# Supply.net
KiCad netlist of a schematic drawn in Altium Designer
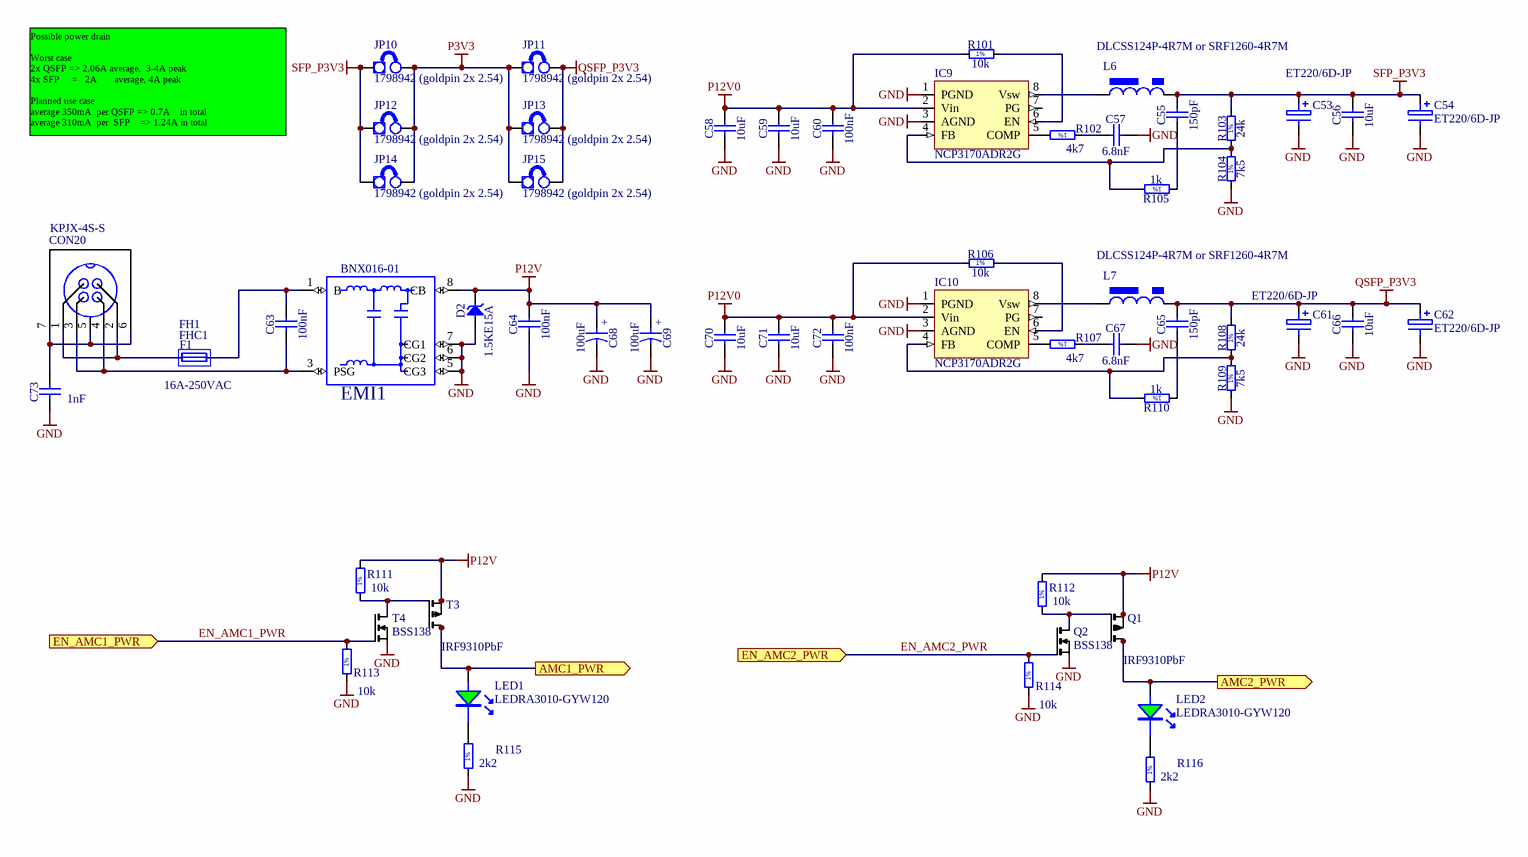
[diagram p0: Supply.SchDoc]

(export (version "E")
  (design (tool "Eeschema 10.0.6"))
  (components
    (comp (ref "C53")
      (value "ET220/6D-JP")
      (footprint "2917_SMDD")
      (description "Tantalium Capacitor")
      (libsource (lib "LIBRARY_SCH") (part "CAP_TANTALIUM"))
    )
    (comp (ref "C54")
      (value "ET220/6D-JP")
      (footprint "2917_SMDD")
      (description "Tantalium Capacitor")
      (libsource (lib "LIBRARY_SCH") (part "CAP_TANTALIUM"))
    )
    (comp (ref "C55")
      (value "150pF")
      (footprint "CAPC1608X87N")
      (description "Non-polarised capacitor")
      (fields
        (field (name "PART NUMBER") "CC0603_150PF_50V_5%_NP0")
        (field (name "VOLTAGE") "50V")
        (field (name "AUTHOR") "CERN DEM JLC")
      )
      (libsource (lib "Capacitors") (part "Capacitor - non polarized"))
    )
    (comp (ref "C56")
      (value "10uF")
      (footprint "CAPC2012X135N")
      (description "Non-polarised capacitor")
      (fields
        (field (name "PART NUMBER") "CC0805_10UF_10V_10%_X7R")
        (field (name "VOLTAGE") "10V")
        (field (name "AUTHOR") "CERN DEM JLC")
      )
      (libsource (lib "Capacitors") (part "Capacitor - non polarized"))
    )
    (comp (ref "C57")
      (value "6.8nF")
      (footprint "CAPC1608X87N")
      (description "Non-polarised capacitor")
      (fields
        (field (name "PART NUMBER") "CC0603_6.8NF_50V_5%_C0G")
        (field (name "VOLTAGE") "50V")
        (field (name "AUTHOR") "CERN DEM JLC")
      )
      (libsource (lib "Capacitors") (part "Capacitor - non polarized"))
    )
    (comp (ref "C58")
      (value "10uF")
      (footprint "CAPC3216X140N")
      (description "Non-polarised capacitor")
      (fields
        (field (name "PART NUMBER") "CC1206_10UF_16V_10%_X7R")
        (field (name "VOLTAGE") "16V")
        (field (name "AUTHOR") "CERN DEM JLC")
      )
      (libsource (lib "Capacitors") (part "Capacitor - non polarized"))
    )
    (comp (ref "C59")
      (value "10uF")
      (footprint "CAPC3216X140N")
      (description "Non-polarised capacitor")
      (fields
        (field (name "PART NUMBER") "CC1206_10UF_16V_10%_X7R")
        (field (name "VOLTAGE") "16V")
        (field (name "AUTHOR") "CERN DEM JLC")
      )
      (libsource (lib "Capacitors") (part "Capacitor - non polarized"))
    )
    (comp (ref "C60")
      (value "100nF")
      (footprint "CAPC1005X55N")
      (description "Non-polarised capacitor")
      (fields
        (field (name "PART NUMBER") "CC0402_100NF_16V_10%_X5R")
        (field (name "VOLTAGE") "16V")
        (field (name "AUTHOR") "CERN DEM JLC")
      )
      (libsource (lib "Capacitors") (part "Capacitor - non polarized"))
    )
    (comp (ref "C61")
      (value "ET220/6D-JP")
      (footprint "2917_SMDD")
      (description "Tantalium Capacitor")
      (libsource (lib "LIBRARY_SCH") (part "CAP_TANTALIUM"))
    )
    (comp (ref "C62")
      (value "ET220/6D-JP")
      (footprint "2917_SMDD")
      (description "Tantalium Capacitor")
      (libsource (lib "LIBRARY_SCH") (part "CAP_TANTALIUM"))
    )
    (comp (ref "C63")
      (value "100nF")
      (footprint "CAPC1005X55N")
      (description "Non-polarised capacitor")
      (fields
        (field (name "PART NUMBER") "CC0402_100NF_16V_10%_X5R")
        (field (name "VOLTAGE") "16V")
        (field (name "AUTHOR") "CERN DEM JLC")
      )
      (libsource (lib "Capacitors") (part "Capacitor - non polarized"))
    )
    (comp (ref "C64")
      (value "100nF")
      (footprint "CAPC1005X55N")
      (description "Non-polarised capacitor")
      (fields
        (field (name "PART NUMBER") "CC0402_100NF_16V_10%_X5R")
        (field (name "VOLTAGE") "16V")
        (field (name "AUTHOR") "CERN DEM JLC")
      )
      (libsource (lib "Capacitors") (part "Capacitor - non polarized"))
    )
    (comp (ref "C65")
      (value "150pF")
      (footprint "CAPC1608X87N")
      (description "Non-polarised capacitor")
      (fields
        (field (name "PART NUMBER") "CC0603_150PF_50V_5%_NP0")
        (field (name "VOLTAGE") "50V")
        (field (name "AUTHOR") "CERN DEM JLC")
      )
      (libsource (lib "Capacitors") (part "Capacitor - non polarized"))
    )
    (comp (ref "C66")
      (value "10uF")
      (footprint "CAPC2012X135N")
      (description "Non-polarised capacitor")
      (fields
        (field (name "PART NUMBER") "CC0805_10UF_10V_10%_X7R")
        (field (name "VOLTAGE") "10V")
        (field (name "AUTHOR") "CERN DEM JLC")
      )
      (libsource (lib "Capacitors") (part "Capacitor - non polarized"))
    )
    (comp (ref "C67")
      (value "6.8nF")
      (footprint "CAPC1608X87N")
      (description "Non-polarised capacitor")
      (fields
        (field (name "PART NUMBER") "CC0603_6.8NF_50V_5%_C0G")
        (field (name "VOLTAGE") "50V")
        (field (name "AUTHOR") "CERN DEM JLC")
      )
      (libsource (lib "Capacitors") (part "Capacitor - non polarized"))
    )
    (comp (ref "C68")
      (value "100uF")
      (footprint "CAPMP7343X430N")
      (description "Polarised capacitor")
      (fields
        (field (name "PART NUMBER") "CTE7343-43_100UF_20V_10%_LESR0150")
        (field (name "VOLTAGE") "20V")
        (field (name "AUTHOR") "CERN DEM JLC")
      )
      (libsource (lib "Capacitors") (part "Capacitor - polarized"))
    )
    (comp (ref "C69")
      (value "100uF")
      (footprint "CAPMP7343X430N")
      (description "Polarised capacitor")
      (fields
        (field (name "PART NUMBER") "CTE7343-43_100UF_20V_10%_LESR0150")
        (field (name "VOLTAGE") "20V")
        (field (name "AUTHOR") "CERN DEM JLC")
      )
      (libsource (lib "Capacitors") (part "Capacitor - polarized"))
    )
    (comp (ref "C70")
      (value "10uF")
      (footprint "CAPC3216X140N")
      (description "Non-polarised capacitor")
      (fields
        (field (name "PART NUMBER") "CC1206_10UF_16V_10%_X7R")
        (field (name "VOLTAGE") "16V")
        (field (name "AUTHOR") "CERN DEM JLC")
      )
      (libsource (lib "Capacitors") (part "Capacitor - non polarized"))
    )
    (comp (ref "C71")
      (value "10uF")
      (footprint "CAPC3216X140N")
      (description "Non-polarised capacitor")
      (fields
        (field (name "PART NUMBER") "CC1206_10UF_16V_10%_X7R")
        (field (name "VOLTAGE") "16V")
        (field (name "AUTHOR") "CERN DEM JLC")
      )
      (libsource (lib "Capacitors") (part "Capacitor - non polarized"))
    )
    (comp (ref "C72")
      (value "100nF")
      (footprint "CAPC1005X55N")
      (description "Non-polarised capacitor")
      (fields
        (field (name "PART NUMBER") "CC0402_100NF_16V_10%_X5R")
        (field (name "VOLTAGE") "16V")
        (field (name "AUTHOR") "CERN DEM JLC")
      )
      (libsource (lib "Capacitors") (part "Capacitor - non polarized"))
    )
    (comp (ref "C73")
      (value "1nF")
      (footprint "CAPC3216X140N")
      (description "Non-polarised capacitor")
      (fields
        (field (name "PART NUMBER") "CC1206_1NF_100V_5%_NP0")
        (field (name "VOLTAGE") "100V")
        (field (name "AUTHOR") "CERN DEM JLC")
      )
      (libsource (lib "Capacitors") (part "Capacitor - non polarized"))
    )
    (comp (ref "CON20")
      (value "KPJX-4S-S")
      (footprint "CON_KPJX-4S-S")
      (description "7.5A DC connector")
      (libsource (lib "LIBRARY_SCH") (part "CON_DC_7.5A_4pin"))
    )
    (comp (ref "D2")
      (value "1.5KE15A")
      (footprint "VISHAY_1.5KE")
      (description "Transient Voltage Suppressor Diode (Uni-Directional)")
      (fields
        (field (name "VOLTAGE") "15V")
        (field (name "POWER") "1500W")
        (field (name "AUTHOR") "CERN DEM JLC")
      )
      (libsource (lib "ICs And Semiconductors") (part "Diode TVS Uni-Directional"))
    )
    (comp (ref "EMI1")
      (value "BNX016-01")
      (footprint "BNX016-01")
      (description "FILTER EMI 50MOHM 15A .1M-1GHZ")
      (fields (field (name "MANF") "MURATA") (field (name "OWNER") "3709"))
      (libsource (lib "LIBRARY_SCH") (part "L_CMC_BNX016-01.1"))
    )
    (comp (ref "F1")
      (value "16A-250VAC")
      (footprint "FUSE_5X20_GLASS_h")
      (description "Fuse")
      (fields
        (field (name "PART NUMBER") "FUSE_SCHURTER_0034.3129_h")
        (field (name "MANUFACTURER") "SCHURTER")
        (field (name "AUTHOR") "CERN DEM JLC")
      )
      (libsource (lib "Eletro-mechanical") (part "Fuse No Pin"))
    )
    (comp (ref "FH1")
      (value "Fuse Holder")
      (footprint "FUSH_SCHURTER_OGN")
      (fields
        (field (name "PART NUMBER") "FUSH_SCHURTER-OGN_0031.8211")
        (field (name "MANUFACTURER") "SCHURTER")
        (field (name "MANUFACTURER PART NUMBER") "0031.8211")
        (field (name "AUTHOR") "CERN DEM JLC")
      )
      (libsource (lib "Eletro-mechanical") (part "Fuse Holder"))
    )
    (comp (ref "FHC1")
      (value "Fuse Holder Cover No Pin")
      (footprint "FUSHC_SCHURTER_0853.0551")
      (fields
        (field (name "PART NUMBER") "FUSHC_SCHURTER_0853.0551")
        (field (name "MANUFACTURER") "SCHURTER")
        (field (name "MANUFACTURER PART NUMBER") "0853.0551")
        (field (name "AUTHOR") "CERN DEM JLC")
      )
      (libsource (lib "Eletro-mechanical") (part "Fuse Holder Cover No Pin"))
    )
    (comp (ref "IC9")
      (value "NCP3170ADR2G")
      (footprint "so-8")
      (description "4.5V to 18V, 3A synch buck")
      (libsource (lib "LIBRARY_SCH") (part "PWM_NCP3170"))
    )
    (comp (ref "IC10")
      (value "NCP3170ADR2G")
      (footprint "so-8")
      (description "4.5V to 18V, 3A synch buck")
      (libsource (lib "LIBRARY_SCH") (part "PWM_NCP3170"))
    )
    (comp (ref "JP10")
      (value "1798942 (goldpin 2x 2.54)")
      (footprint "HEADER2x1 2.54mm")
      (description "Jumper")
      (libsource (lib "Misc") (part "JUMPER"))
    )
    (comp (ref "JP11")
      (value "1798942 (goldpin 2x 2.54)")
      (footprint "HEADER2x1 2.54mm")
      (description "Jumper")
      (libsource (lib "Misc") (part "JUMPER"))
    )
    (comp (ref "JP12")
      (value "1798942 (goldpin 2x 2.54)")
      (footprint "HEADER2x1 2.54mm")
      (description "Jumper")
      (libsource (lib "Misc") (part "JUMPER"))
    )
    (comp (ref "JP13")
      (value "1798942 (goldpin 2x 2.54)")
      (footprint "HEADER2x1 2.54mm")
      (description "Jumper")
      (libsource (lib "Misc") (part "JUMPER"))
    )
    (comp (ref "JP14")
      (value "1798942 (goldpin 2x 2.54)")
      (footprint "HEADER2x1 2.54mm")
      (description "Jumper")
      (libsource (lib "Misc") (part "JUMPER"))
    )
    (comp (ref "JP15")
      (value "1798942 (goldpin 2x 2.54)")
      (footprint "HEADER2x1 2.54mm")
      (description "Jumper")
      (libsource (lib "Misc") (part "JUMPER"))
    )
    (comp (ref "L6")
      (value "DLCSS124P-4R7M or SRF1260-4R7M")
      (footprint "choke_DLCSS124")
      (description "Shielded Ferrite base SMD Power Choke DLCSS124P Series 4.7uH, 20%, 5.7A, 0.018R, 750pcs/reel")
      (libsource (lib "LIBRARY_SCH") (part "L_POWER_CSS124_6.8uH"))
    )
    (comp (ref "L7")
      (value "DLCSS124P-4R7M or SRF1260-4R7M")
      (footprint "choke_DLCSS124")
      (description "Shielded Ferrite base SMD Power Choke DLCSS124P Series 4.7uH, 20%, 5.7A, 0.018R, 750pcs/reel")
      (libsource (lib "LIBRARY_SCH") (part "L_POWER_CSS124_6.8uH"))
    )
    (comp (ref "LED1")
      (value "LEDRA3010-GYW120")
      (footprint "LED_KPA3010_G")
      (description "LED (Maritex)")
      (libsource (lib "LIBRARY_SCH") (part "LED_SMD_90deg_G"))
    )
    (comp (ref "LED2")
      (value "LEDRA3010-GYW120")
      (footprint "LED_KPA3010_G")
      (description "LED (Maritex)")
      (libsource (lib "LIBRARY_SCH") (part "LED_SMD_90deg_G"))
    )
    (comp (ref "Q1")
      (value "IRF9310PbF")
      (footprint "so-8")
      (description "PMOS 30V, 4.6mR, 20A, 2.5W")
      (libsource (lib "LIBRARY_SCH") (part "Q_IRF9310"))
    )
    (comp (ref "Q2")
      (value "BSS138")
      (footprint "SOT95P251X112-3N")
      (libsource (lib "LIBRARY_SCH") (part "Q_BSS138"))
    )
    (comp (ref "R101")
      (value "10k")
      (footprint "RESC1005X40N")
      (description "Resistor - 1%")
      (fields
        (field (name "PART NUMBER") "R0402_10K_1%_0.0625W_100PPM")
        (field (name "POWER") "0.0625W")
        (field (name "AUTHOR") "CERN DEM JLC")
      )
      (libsource (lib "Resistors") (part "Resistor - 1%"))
    )
    (comp (ref "R102")
      (value "4k7")
      (footprint "RESC1005X40N")
      (description "Resistor - 1%")
      (fields
        (field (name "PART NUMBER") "R0402_4K7_1%_0.0625W_100PPM")
        (field (name "POWER") "0.0625W")
        (field (name "AUTHOR") "CERN DEM JLC")
      )
      (libsource (lib "Resistors") (part "Resistor - 1%"))
    )
    (comp (ref "R103")
      (value "24k")
      (footprint "RESC1608X55N")
      (description "Resistor - 1%")
      (fields
        (field (name "PART NUMBER") "R0603_24K_1%_0.1W_100PPM")
        (field (name "POWER") "0.1W")
        (field (name "AUTHOR") "CERN DEM JLC")
      )
      (libsource (lib "Resistors") (part "Resistor - 1%"))
    )
    (comp (ref "R104")
      (value "7k5")
      (footprint "RESC1608X55N")
      (description "Resistor - 1%")
      (fields
        (field (name "PART NUMBER") "R0603_7K5_1%_0.1W_100PPM")
        (field (name "POWER") "0.1W")
        (field (name "AUTHOR") "CERN DEM JLC")
      )
      (libsource (lib "Resistors") (part "Resistor - 1%"))
    )
    (comp (ref "R105")
      (value "1k")
      (footprint "RESC1005X40N")
      (description "Resistor - 1%")
      (fields
        (field (name "PART NUMBER") "R0402_1K_1%_0.0625W_100PPM")
        (field (name "POWER") "0.0625W")
        (field (name "AUTHOR") "CERN DEM JLC")
      )
      (libsource (lib "Resistors") (part "Resistor - 1%"))
    )
    (comp (ref "R106")
      (value "10k")
      (footprint "RESC1005X40N")
      (description "Resistor - 1%")
      (fields
        (field (name "PART NUMBER") "R0402_10K_1%_0.0625W_100PPM")
        (field (name "POWER") "0.0625W")
        (field (name "AUTHOR") "CERN DEM JLC")
      )
      (libsource (lib "Resistors") (part "Resistor - 1%"))
    )
    (comp (ref "R107")
      (value "4k7")
      (footprint "RESC1005X40N")
      (description "Resistor - 1%")
      (fields
        (field (name "PART NUMBER") "R0402_4K7_1%_0.0625W_100PPM")
        (field (name "POWER") "0.0625W")
        (field (name "AUTHOR") "CERN DEM JLC")
      )
      (libsource (lib "Resistors") (part "Resistor - 1%"))
    )
    (comp (ref "R108")
      (value "24k")
      (footprint "RESC1608X55N")
      (description "Resistor - 1%")
      (fields
        (field (name "PART NUMBER") "R0603_24K_1%_0.1W_100PPM")
        (field (name "POWER") "0.1W")
        (field (name "AUTHOR") "CERN DEM JLC")
      )
      (libsource (lib "Resistors") (part "Resistor - 1%"))
    )
    (comp (ref "R109")
      (value "7k5")
      (footprint "RESC1608X55N")
      (description "Resistor - 1%")
      (fields
        (field (name "PART NUMBER") "R0603_7K5_1%_0.1W_100PPM")
        (field (name "POWER") "0.1W")
        (field (name "AUTHOR") "CERN DEM JLC")
      )
      (libsource (lib "Resistors") (part "Resistor - 1%"))
    )
    (comp (ref "R110")
      (value "1k")
      (footprint "RESC1005X40N")
      (description "Resistor - 1%")
      (fields
        (field (name "PART NUMBER") "R0402_1K_1%_0.0625W_100PPM")
        (field (name "POWER") "0.0625W")
        (field (name "AUTHOR") "CERN DEM JLC")
      )
      (libsource (lib "Resistors") (part "Resistor - 1%"))
    )
    (comp (ref "R111")
      (value "10k")
      (footprint "RESC1005X40N")
      (description "Resistor - 1%")
      (fields
        (field (name "PART NUMBER") "R0402_10K_1%_0.0625W_100PPM")
        (field (name "POWER") "0.0625W")
        (field (name "AUTHOR") "CERN DEM JLC")
      )
      (libsource (lib "Resistors") (part "Resistor - 1%"))
    )
    (comp (ref "R112")
      (value "10k")
      (footprint "RESC1005X40N")
      (description "Resistor - 1%")
      (fields
        (field (name "PART NUMBER") "R0402_10K_1%_0.0625W_100PPM")
        (field (name "POWER") "0.0625W")
        (field (name "AUTHOR") "CERN DEM JLC")
      )
      (libsource (lib "Resistors") (part "Resistor - 1%"))
    )
    (comp (ref "R113")
      (value "10k")
      (footprint "RESC1005X40N")
      (description "Resistor - 1%")
      (fields
        (field (name "PART NUMBER") "R0402_10K_1%_0.0625W_100PPM")
        (field (name "POWER") "0.0625W")
        (field (name "AUTHOR") "CERN DEM JLC")
      )
      (libsource (lib "Resistors") (part "Resistor - 1%"))
    )
    (comp (ref "R114")
      (value "10k")
      (footprint "RESC1005X40N")
      (description "Resistor - 1%")
      (fields
        (field (name "PART NUMBER") "R0402_10K_1%_0.0625W_100PPM")
        (field (name "POWER") "0.0625W")
        (field (name "AUTHOR") "CERN DEM JLC")
      )
      (libsource (lib "Resistors") (part "Resistor - 1%"))
    )
    (comp (ref "R115")
      (value "2k2")
      (footprint "RESC1005X40N")
      (description "Resistor - 1%")
      (fields
        (field (name "PART NUMBER") "R0402_2K2_1%_0.0625W_100PPM")
        (field (name "POWER") "0.0625W")
        (field (name "AUTHOR") "CERN DEM JLC")
      )
      (libsource (lib "Resistors") (part "Resistor - 1%"))
    )
    (comp (ref "R116")
      (value "2k2")
      (footprint "RESC1005X40N")
      (description "Resistor - 1%")
      (fields
        (field (name "PART NUMBER") "R0402_2K2_1%_0.0625W_100PPM")
        (field (name "POWER") "0.0625W")
        (field (name "AUTHOR") "CERN DEM JLC")
      )
      (libsource (lib "Resistors") (part "Resistor - 1%"))
    )
    (comp (ref "T3")
      (value "IRF9310PbF")
      (footprint "so-8")
      (description "PMOS 30V, 4.6mR, 20A, 2.5W")
      (libsource (lib "LIBRARY_SCH") (part "Q_IRF9310"))
    )
    (comp (ref "T4")
      (value "BSS138")
      (footprint "SOT95P251X112-3N")
      (libsource (lib "LIBRARY_SCH") (part "Q_BSS138"))
    )
  )
  (nets
    (net (code "1") (name "/AMC1_PWR") (class "Default")
      (node (ref "LED1") (pin "A") (pinfunction "A_A") (pintype "passive"))
      (node (ref "T3") (pin "5") (pinfunction "D1_5") (pintype "open_collector"))
      (node (ref "T3") (pin "6") (pinfunction "D1_6") (pintype "open_collector"))
      (node (ref "T3") (pin "7") (pinfunction "D1_7") (pintype "open_collector"))
      (node (ref "T3") (pin "8") (pinfunction "D1_8") (pintype "open_collector"))
    )
    (net (code "2") (name "/AMC2_PWR") (class "Default")
      (node (ref "LED2") (pin "A") (pinfunction "A_A") (pintype "passive"))
      (node (ref "Q1") (pin "5") (pinfunction "D1_5") (pintype "open_collector"))
      (node (ref "Q1") (pin "6") (pinfunction "D1_6") (pintype "open_collector"))
      (node (ref "Q1") (pin "7") (pinfunction "D1_7") (pintype "open_collector"))
      (node (ref "Q1") (pin "8") (pinfunction "D1_8") (pintype "open_collector"))
    )
    (net (code "3") (name "/EN_AMC1_PWR") (class "Default")
      (node (ref "R113") (pin "2") (pinfunction "2_2") (pintype "passive"))
      (node (ref "T4") (pin "1") (pinfunction "G_1") (pintype "input"))
    )
    (net (code "4") (name "/EN_AMC2_PWR") (class "Default")
      (node (ref "Q2") (pin "1") (pinfunction "G_1") (pintype "input"))
      (node (ref "R114") (pin "2") (pinfunction "2_2") (pintype "passive"))
    )
    (net (code "5") (name "GND") (class "Default")
      (node (ref "C53") (pin "2") (pinfunction "2_2") (pintype "passive"))
      (node (ref "C54") (pin "2") (pinfunction "2_2") (pintype "passive"))
      (node (ref "C56") (pin "1") (pinfunction "1_1") (pintype "passive"))
      (node (ref "C57") (pin "2") (pinfunction "2_2") (pintype "passive"))
      (node (ref "C58") (pin "1") (pinfunction "1_1") (pintype "passive"))
      (node (ref "C59") (pin "1") (pinfunction "1_1") (pintype "passive"))
      (node (ref "C60") (pin "1") (pinfunction "1_1") (pintype "passive"))
      (node (ref "C61") (pin "2") (pinfunction "2_2") (pintype "passive"))
      (node (ref "C62") (pin "2") (pinfunction "2_2") (pintype "passive"))
      (node (ref "C64") (pin "1") (pinfunction "1_1") (pintype "passive"))
      (node (ref "C66") (pin "1") (pinfunction "1_1") (pintype "passive"))
      (node (ref "C67") (pin "2") (pinfunction "2_2") (pintype "passive"))
      (node (ref "C68") (pin "2") (pinfunction "2_2") (pintype "passive"))
      (node (ref "C69") (pin "2") (pinfunction "2_2") (pintype "passive"))
      (node (ref "C70") (pin "1") (pinfunction "1_1") (pintype "passive"))
      (node (ref "C71") (pin "1") (pinfunction "1_1") (pintype "passive"))
      (node (ref "C72") (pin "1") (pinfunction "1_1") (pintype "passive"))
      (node (ref "C73") (pin "1") (pinfunction "1_1") (pintype "passive"))
      (node (ref "D2") (pin "2") (pinfunction "A_2") (pintype "passive"))
      (node (ref "EMI1") (pin "5") (pinfunction "CG3_5") (pintype "bidirectional"))
      (node (ref "EMI1") (pin "6") (pinfunction "CG2_6") (pintype "bidirectional"))
      (node (ref "EMI1") (pin "7") (pinfunction "CG1_7") (pintype "bidirectional"))
      (node (ref "IC10") (pin "1") (pinfunction "PGND_1") (pintype "power_in"))
      (node (ref "IC10") (pin "3") (pinfunction "AGND_3") (pintype "power_in"))
      (node (ref "IC9") (pin "1") (pinfunction "PGND_1") (pintype "power_in"))
      (node (ref "IC9") (pin "3") (pinfunction "AGND_3") (pintype "power_in"))
      (node (ref "Q2") (pin "2") (pinfunction "S_2") (pintype "passive"))
      (node (ref "R104") (pin "1") (pinfunction "1_1") (pintype "passive"))
      (node (ref "R109") (pin "1") (pinfunction "1_1") (pintype "passive"))
      (node (ref "R113") (pin "1") (pinfunction "1_1") (pintype "passive"))
      (node (ref "R114") (pin "1") (pinfunction "1_1") (pintype "passive"))
      (node (ref "R115") (pin "1") (pinfunction "1_1") (pintype "passive"))
      (node (ref "R116") (pin "1") (pinfunction "1_1") (pintype "passive"))
      (node (ref "T4") (pin "2") (pinfunction "S_2") (pintype "passive"))
    )
    (net (code "6") (name "Net-(C55-Pad1)") (class "Default")
      (node (ref "C55") (pin "1") (pinfunction "1_1") (pintype "passive"))
      (node (ref "R105") (pin "1") (pinfunction "1_1") (pintype "passive"))
    )
    (net (code "7") (name "Net-(C57-Pad1)") (class "Default")
      (node (ref "C57") (pin "1") (pinfunction "1_1") (pintype "passive"))
      (node (ref "R102") (pin "1") (pinfunction "1_1") (pintype "passive"))
    )
    (net (code "8") (name "Net-(C65-Pad1)") (class "Default")
      (node (ref "C65") (pin "1") (pinfunction "1_1") (pintype "passive"))
      (node (ref "R110") (pin "1") (pinfunction "1_1") (pintype "passive"))
    )
    (net (code "9") (name "Net-(C67-Pad1)") (class "Default")
      (node (ref "C67") (pin "1") (pinfunction "1_1") (pintype "passive"))
      (node (ref "R107") (pin "1") (pinfunction "1_1") (pintype "passive"))
    )
    (net (code "10") (name "Net-(C73-Pad2)") (class "Default")
      (node (ref "C73") (pin "2") (pinfunction "2_2") (pintype "passive"))
      (node (ref "CON20") (pin "5") (pinfunction "5_5") (pintype "passive"))
      (node (ref "CON20") (pin "6") (pinfunction "6_6") (pintype "passive"))
      (node (ref "CON20") (pin "7") (pinfunction "7_7") (pintype "passive"))
    )
    (net (code "11") (name "Net-(CON20-Pad1)") (class "Default")
      (node (ref "CON20") (pin "1") (pinfunction "1_1") (pintype "passive"))
      (node (ref "CON20") (pin "2") (pinfunction "2_2") (pintype "passive"))
      (node (ref "FH1") (pin "1") (pinfunction "1_1") (pintype "passive"))
    )
    (net (code "12") (name "Net-(EMI1-B)") (class "Default")
      (node (ref "C63") (pin "2") (pinfunction "2_2") (pintype "passive"))
      (node (ref "EMI1") (pin "1") (pinfunction "B_1") (pintype "bidirectional"))
      (node (ref "FH1") (pin "2") (pinfunction "2_2") (pintype "passive"))
    )
    (net (code "13") (name "Net-(EMI1-PSG)") (class "Default")
      (node (ref "C63") (pin "1") (pinfunction "1_1") (pintype "passive"))
      (node (ref "CON20") (pin "3") (pinfunction "3_3") (pintype "passive"))
      (node (ref "CON20") (pin "4") (pinfunction "4_4") (pintype "passive"))
      (node (ref "EMI1") (pin "3") (pinfunction "PSG_3") (pintype "bidirectional"))
    )
    (net (code "14") (name "Net-(IC9-COMP)") (class "Default")
      (node (ref "IC9") (pin "5") (pinfunction "COMP_5") (pintype "passive"))
      (node (ref "R102") (pin "2") (pinfunction "2_2") (pintype "passive"))
    )
    (net (code "15") (name "Net-(IC9-EN)") (class "Default")
      (node (ref "IC9") (pin "6") (pinfunction "EN_6") (pintype "input"))
      (node (ref "R101") (pin "2") (pinfunction "2_2") (pintype "passive"))
    )
    (net (code "16") (name "Net-(IC9-FB)") (class "Default")
      (node (ref "IC9") (pin "4") (pinfunction "FB_4") (pintype "input"))
      (node (ref "R103") (pin "1") (pinfunction "1_1") (pintype "passive"))
      (node (ref "R104") (pin "2") (pinfunction "2_2") (pintype "passive"))
      (node (ref "R105") (pin "2") (pinfunction "2_2") (pintype "passive"))
    )
    (net (code "17") (name "Net-(IC9-Vsw)") (class "Default")
      (node (ref "IC9") (pin "8") (pinfunction "Vsw_8") (pintype "output"))
      (node (ref "L6") (pin "1") (pintype "passive"))
    )
    (net (code "18") (name "Net-(IC10-COMP)") (class "Default")
      (node (ref "IC10") (pin "5") (pinfunction "COMP_5") (pintype "passive"))
      (node (ref "R107") (pin "2") (pinfunction "2_2") (pintype "passive"))
    )
    (net (code "19") (name "Net-(IC10-EN)") (class "Default")
      (node (ref "IC10") (pin "6") (pinfunction "EN_6") (pintype "input"))
      (node (ref "R106") (pin "2") (pinfunction "2_2") (pintype "passive"))
    )
    (net (code "20") (name "Net-(IC10-FB)") (class "Default")
      (node (ref "IC10") (pin "4") (pinfunction "FB_4") (pintype "input"))
      (node (ref "R108") (pin "1") (pinfunction "1_1") (pintype "passive"))
      (node (ref "R109") (pin "2") (pinfunction "2_2") (pintype "passive"))
      (node (ref "R110") (pin "2") (pinfunction "2_2") (pintype "passive"))
    )
    (net (code "21") (name "Net-(IC10-Vsw)") (class "Default")
      (node (ref "IC10") (pin "8") (pinfunction "Vsw_8") (pintype "output"))
      (node (ref "L7") (pin "1") (pintype "passive"))
    )
    (net (code "22") (name "Net-(LED1-PadK)") (class "Default")
      (node (ref "LED1") (pin "K") (pinfunction "K_K") (pintype "passive"))
      (node (ref "R115") (pin "2") (pinfunction "2_2") (pintype "passive"))
    )
    (net (code "23") (name "Net-(LED2-PadK)") (class "Default")
      (node (ref "LED2") (pin "K") (pinfunction "K_K") (pintype "passive"))
      (node (ref "R116") (pin "2") (pinfunction "2_2") (pintype "passive"))
    )
    (net (code "24") (name "Net-(Q1-G1)") (class "Default")
      (node (ref "Q1") (pin "4") (pinfunction "G1_4") (pintype "input"))
      (node (ref "Q2") (pin "3") (pinfunction "D_3") (pintype "passive"))
      (node (ref "R112") (pin "1") (pinfunction "1_1") (pintype "passive"))
    )
    (net (code "25") (name "Net-(T3-G1)") (class "Default")
      (node (ref "R111") (pin "1") (pinfunction "1_1") (pintype "passive"))
      (node (ref "T3") (pin "4") (pinfunction "G1_4") (pintype "input"))
      (node (ref "T4") (pin "3") (pinfunction "D_3") (pintype "passive"))
    )
    (net (code "26") (name "P3V3") (class "Default")
      (node (ref "JP10") (pin "2") (pinfunction "E2_2") (pintype "passive"))
      (node (ref "JP11") (pin "1") (pinfunction "E1_1") (pintype "passive"))
      (node (ref "JP12") (pin "2") (pinfunction "E2_2") (pintype "passive"))
      (node (ref "JP13") (pin "1") (pinfunction "E1_1") (pintype "passive"))
      (node (ref "JP14") (pin "2") (pinfunction "E2_2") (pintype "passive"))
      (node (ref "JP15") (pin "1") (pinfunction "E1_1") (pintype "passive"))
    )
    (net (code "27") (name "P12V") (class "Default")
      (node (ref "C64") (pin "2") (pinfunction "2_2") (pintype "passive"))
      (node (ref "C68") (pin "1") (pinfunction "1_1") (pintype "passive"))
      (node (ref "C69") (pin "1") (pinfunction "1_1") (pintype "passive"))
      (node (ref "D2") (pin "1") (pinfunction "C_1") (pintype "passive"))
      (node (ref "EMI1") (pin "8") (pinfunction "CB_8") (pintype "bidirectional"))
      (node (ref "Q1") (pin "1") (pinfunction "S1_1") (pintype "open_emitter"))
      (node (ref "Q1") (pin "2") (pinfunction "S1_2") (pintype "open_emitter"))
      (node (ref "Q1") (pin "3") (pinfunction "S1_3") (pintype "open_emitter"))
      (node (ref "R111") (pin "2") (pinfunction "2_2") (pintype "passive"))
      (node (ref "R112") (pin "2") (pinfunction "2_2") (pintype "passive"))
      (node (ref "T3") (pin "1") (pinfunction "S1_1") (pintype "open_emitter"))
      (node (ref "T3") (pin "2") (pinfunction "S1_2") (pintype "open_emitter"))
      (node (ref "T3") (pin "3") (pinfunction "S1_3") (pintype "open_emitter"))
    )
    (net (code "28") (name "P12V0") (class "Default")
      (node (ref "C58") (pin "2") (pinfunction "2_2") (pintype "passive"))
      (node (ref "C59") (pin "2") (pinfunction "2_2") (pintype "passive"))
      (node (ref "C60") (pin "2") (pinfunction "2_2") (pintype "passive"))
      (node (ref "C70") (pin "2") (pinfunction "2_2") (pintype "passive"))
      (node (ref "C71") (pin "2") (pinfunction "2_2") (pintype "passive"))
      (node (ref "C72") (pin "2") (pinfunction "2_2") (pintype "passive"))
      (node (ref "IC10") (pin "2") (pinfunction "Vin_2") (pintype "power_in"))
      (node (ref "IC9") (pin "2") (pinfunction "Vin_2") (pintype "power_in"))
      (node (ref "R101") (pin "1") (pinfunction "1_1") (pintype "passive"))
      (node (ref "R106") (pin "1") (pinfunction "1_1") (pintype "passive"))
    )
    (net (code "29") (name "QSFP_P3V3") (class "Default")
      (node (ref "C61") (pin "1") (pinfunction "1_1") (pintype "passive"))
      (node (ref "C62") (pin "1") (pinfunction "1_1") (pintype "passive"))
      (node (ref "C65") (pin "2") (pinfunction "2_2") (pintype "passive"))
      (node (ref "C66") (pin "2") (pinfunction "2_2") (pintype "passive"))
      (node (ref "JP11") (pin "2") (pinfunction "E2_2") (pintype "passive"))
      (node (ref "JP13") (pin "2") (pinfunction "E2_2") (pintype "passive"))
      (node (ref "JP15") (pin "2") (pinfunction "E2_2") (pintype "passive"))
      (node (ref "L7") (pin "2") (pintype "passive"))
      (node (ref "R108") (pin "2") (pinfunction "2_2") (pintype "passive"))
    )
    (net (code "30") (name "SFP_P3V3") (class "Default")
      (node (ref "C53") (pin "1") (pinfunction "1_1") (pintype "passive"))
      (node (ref "C54") (pin "1") (pinfunction "1_1") (pintype "passive"))
      (node (ref "C55") (pin "2") (pinfunction "2_2") (pintype "passive"))
      (node (ref "C56") (pin "2") (pinfunction "2_2") (pintype "passive"))
      (node (ref "JP10") (pin "1") (pinfunction "E1_1") (pintype "passive"))
      (node (ref "JP12") (pin "1") (pinfunction "E1_1") (pintype "passive"))
      (node (ref "JP14") (pin "1") (pinfunction "E1_1") (pintype "passive"))
      (node (ref "L6") (pin "2") (pintype "passive"))
      (node (ref "R103") (pin "2") (pinfunction "2_2") (pintype "passive"))
    )
    (net (code "31") (name "unconnected-(IC9-PG-Pad7)") (class "Default")
      (node (ref "IC9") (pin "7") (pinfunction "PG_7") (pintype "output"))
    )
    (net (code "32") (name "unconnected-(IC10-PG-Pad7)") (class "Default")
      (node (ref "IC10") (pin "7") (pinfunction "PG_7") (pintype "output"))
    )
  )
)
